# Peripherals.net
KiCad netlist of a schematic drawn in Altium Designer
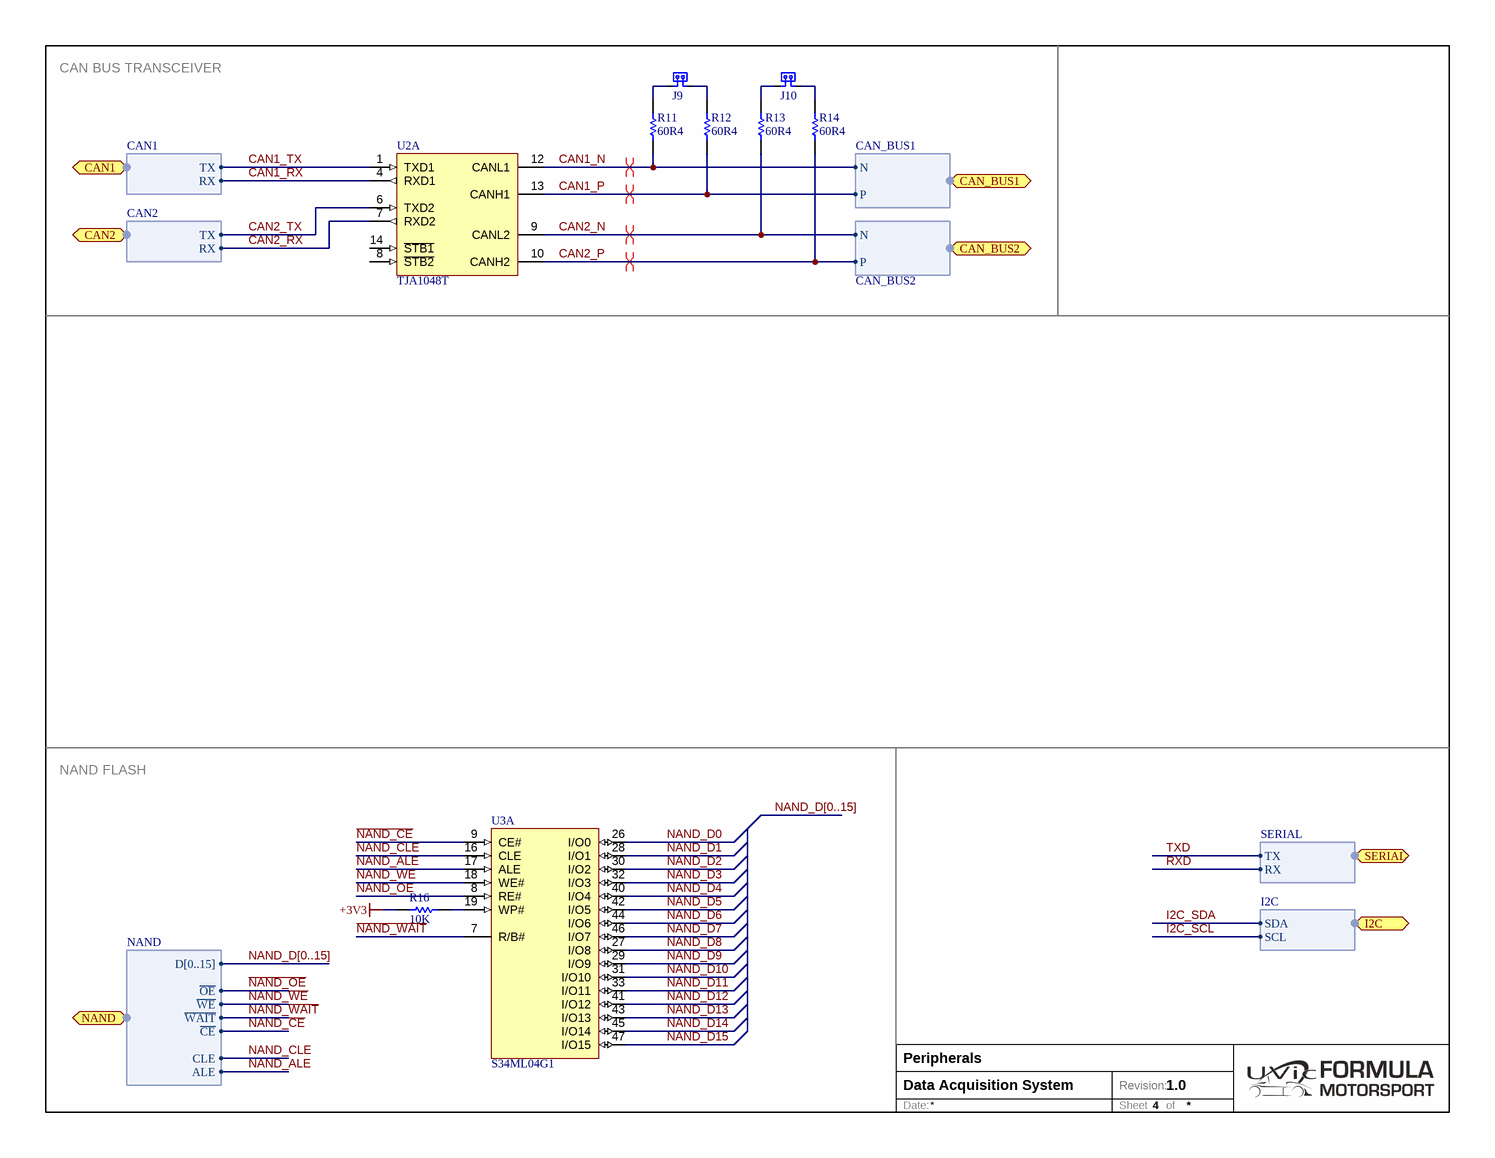
[diagram p0: Peripherals.SchDoc]

(export (version "E")
  (design (tool "Eeschema 10.0.6"))
  (components
    (comp (ref "J9")
      (value "M20-9990246")
      (footprint "M20-9990246")
      (description "2.54mm Header Jumper")
      (libsource (lib "DAQ") (part "JUMPER-1"))
    )
    (comp (ref "J10")
      (value "M20-9990246")
      (footprint "M20-9990246")
      (description "2.54mm Header Jumper")
      (libsource (lib "DAQ") (part "JUMPER-1"))
    )
    (comp (ref "R11")
      (value "60R4")
      (footprint "RES-1206-M")
      (fields
        (field (name "PART NUMBER") "RC1206FR-0760R4L")
        (field (name "TOLERANCE") "±1%")
        (field (name "POWER") "1/4 W")
      )
      (libsource (lib "Resistors") (part "Resistor"))
    )
    (comp (ref "R12")
      (value "60R4")
      (footprint "RES-1206-M")
      (fields
        (field (name "PART NUMBER") "RC1206FR-0760R4L")
        (field (name "TOLERANCE") "±1%")
        (field (name "POWER") "1/4 W")
      )
      (libsource (lib "Resistors") (part "Resistor"))
    )
    (comp (ref "R13")
      (value "60R4")
      (footprint "RES-1206-M")
      (fields
        (field (name "PART NUMBER") "RC1206FR-0760R4L")
        (field (name "TOLERANCE") "±1%")
        (field (name "POWER") "1/4 W")
      )
      (libsource (lib "Resistors") (part "Resistor"))
    )
    (comp (ref "R14")
      (value "60R4")
      (footprint "RES-1206-M")
      (fields
        (field (name "PART NUMBER") "RC1206FR-0760R4L")
        (field (name "TOLERANCE") "±1%")
        (field (name "POWER") "1/4 W")
      )
      (libsource (lib "Resistors") (part "Resistor"))
    )
    (comp (ref "R16")
      (value "10K")
      (footprint "RES-0603-M")
      (fields
        (field (name "PART NUMBER") "RC0603FR-0710KL")
        (field (name "TOLERANCE") "1%")
        (field (name "POWER") "1/10 W")
      )
      (libsource (lib "Resistors") (part "Resistor"))
    )
    (comp (ref "U2")
      (value "TJA1048T")
      (footprint "SOP127P600X175-14N")
      (description "Dual CAN transceiver")
      (libsource (lib "DAQ") (part "TJA1048T"))
    )
    (comp (ref "U3") (value "S34ML04G1") (footprint "48-TSOP") (libsource (lib "DAQ") (part "S34ML04G1")))
  )
  (nets
    (net (code "8") (name "+3V3") (class "Default")
      (node (ref "R16") (pin "2") (pinfunction "2_2") (pintype "passive"))
    )
    (net (code "9") (name "/CAN1_N") (class "Default")
      (node (ref "R11") (pin "2") (pinfunction "2_2") (pintype "passive"))
      (node (ref "U2") (pin "12") (pinfunction "CANL1_12") (pintype "passive"))
    )
    (net (code "10") (name "/CAN1_P") (class "Default")
      (node (ref "R12") (pin "2") (pinfunction "2_2") (pintype "passive"))
      (node (ref "U2") (pin "13") (pinfunction "CANH1_13") (pintype "passive"))
    )
    (net (code "11") (name "/CAN1_RX") (class "Default")
      (node (ref "U2") (pin "4") (pinfunction "RXD1_4") (pintype "output"))
    )
    (net (code "12") (name "/CAN1_TX") (class "Default")
      (node (ref "U2") (pin "1") (pinfunction "TXD1_1") (pintype "input"))
    )
    (net (code "13") (name "/CAN2_N") (class "Default")
      (node (ref "R13") (pin "2") (pinfunction "2_2") (pintype "passive"))
      (node (ref "U2") (pin "9") (pinfunction "CANL2_9") (pintype "passive"))
    )
    (net (code "14") (name "/CAN2_P") (class "Default")
      (node (ref "R14") (pin "2") (pinfunction "2_2") (pintype "passive"))
      (node (ref "U2") (pin "10") (pinfunction "CANH2_10") (pintype "passive"))
    )
    (net (code "15") (name "/CAN2_RX") (class "Default")
      (node (ref "U2") (pin "7") (pinfunction "RXD2_7") (pintype "output"))
    )
    (net (code "16") (name "/CAN2_TX") (class "Default")
      (node (ref "U2") (pin "6") (pinfunction "TXD2_6") (pintype "input"))
    )
    (net (code "19") (name "/NAND_ALE") (class "Default")
      (node (ref "U3") (pin "17") (pinfunction "ALE_17") (pintype "input"))
    )
    (net (code "20") (name "/NAND_CLE") (class "Default")
      (node (ref "U3") (pin "16") (pinfunction "CLE_16") (pintype "input"))
    )
    (net (code "21") (name "/NAND_D0") (class "Default")
      (node (ref "U3") (pin "26") (pinfunction "I/O0_26") (pintype "bidirectional"))
    )
    (net (code "22") (name "/NAND_D1") (class "Default")
      (node (ref "U3") (pin "28") (pinfunction "I/O1_28") (pintype "bidirectional"))
    )
    (net (code "23") (name "/NAND_D2") (class "Default")
      (node (ref "U3") (pin "30") (pinfunction "I/O2_30") (pintype "bidirectional"))
    )
    (net (code "24") (name "/NAND_D3") (class "Default")
      (node (ref "U3") (pin "32") (pinfunction "I/O3_32") (pintype "bidirectional"))
    )
    (net (code "25") (name "/NAND_D4") (class "Default")
      (node (ref "U3") (pin "40") (pinfunction "I/O4_40") (pintype "bidirectional"))
    )
    (net (code "26") (name "/NAND_D5") (class "Default")
      (node (ref "U3") (pin "42") (pinfunction "I/O5_42") (pintype "bidirectional"))
    )
    (net (code "27") (name "/NAND_D6") (class "Default")
      (node (ref "U3") (pin "44") (pinfunction "I/O6_44") (pintype "bidirectional"))
    )
    (net (code "28") (name "/NAND_D7") (class "Default")
      (node (ref "U3") (pin "46") (pinfunction "I/O7_46") (pintype "bidirectional"))
    )
    (net (code "29") (name "/NAND_D8") (class "Default")
      (node (ref "U3") (pin "27") (pinfunction "I/O8_27") (pintype "bidirectional"))
    )
    (net (code "30") (name "/NAND_D9") (class "Default")
      (node (ref "U3") (pin "29") (pinfunction "I/O9_29") (pintype "bidirectional"))
    )
    (net (code "31") (name "/NAND_D10") (class "Default")
      (node (ref "U3") (pin "31") (pinfunction "I/O10_31") (pintype "bidirectional"))
    )
    (net (code "32") (name "/NAND_D11") (class "Default")
      (node (ref "U3") (pin "33") (pinfunction "I/O11_33") (pintype "bidirectional"))
    )
    (net (code "33") (name "/NAND_D12") (class "Default")
      (node (ref "U3") (pin "41") (pinfunction "I/O12_41") (pintype "bidirectional"))
    )
    (net (code "34") (name "/NAND_D13") (class "Default")
      (node (ref "U3") (pin "43") (pinfunction "I/O13_43") (pintype "bidirectional"))
    )
    (net (code "35") (name "/NAND_D14") (class "Default")
      (node (ref "U3") (pin "45") (pinfunction "I/O14_45") (pintype "bidirectional"))
    )
    (net (code "36") (name "/NAND_D15") (class "Default")
      (node (ref "U3") (pin "47") (pinfunction "I/O15_47") (pintype "bidirectional"))
    )
    (net (code "48") (name "/~{NAND_CE}") (class "Default")
      (node (ref "U3") (pin "9") (pinfunction "CE#_9") (pintype "input"))
    )
    (net (code "49") (name "/~{NAND_OE}") (class "Default")
      (node (ref "U3") (pin "8") (pinfunction "RE#_8") (pintype "input"))
    )
    (net (code "50") (name "/~{NAND_WAIT}") (class "Default")
      (node (ref "U3") (pin "7") (pinfunction "R/B#_7") (pintype "tri_state"))
    )
    (net (code "51") (name "/~{NAND_WE}") (class "Default")
      (node (ref "U3") (pin "18") (pinfunction "WE#_18") (pintype "input"))
    )
    (net (code "52") (name "Net-(J9-Pad1)") (class "Default")
      (node (ref "J9") (pin "1") (pinfunction "1_1") (pintype "passive"))
      (node (ref "R11") (pin "1") (pinfunction "1_1") (pintype "passive"))
    )
    (net (code "53") (name "Net-(J9-Pad2)") (class "Default")
      (node (ref "J9") (pin "2") (pinfunction "2_2") (pintype "passive"))
      (node (ref "R12") (pin "1") (pinfunction "1_1") (pintype "passive"))
    )
    (net (code "54") (name "Net-(J10-Pad1)") (class "Default")
      (node (ref "J10") (pin "1") (pinfunction "1_1") (pintype "passive"))
      (node (ref "R13") (pin "1") (pinfunction "1_1") (pintype "passive"))
    )
    (net (code "55") (name "Net-(J10-Pad2)") (class "Default")
      (node (ref "J10") (pin "2") (pinfunction "2_2") (pintype "passive"))
      (node (ref "R14") (pin "1") (pinfunction "1_1") (pintype "passive"))
    )
    (net (code "56") (name "Net-(U3A-WP#)") (class "Default")
      (node (ref "R16") (pin "1") (pinfunction "1_1") (pintype "passive"))
      (node (ref "U3") (pin "19") (pinfunction "WP#_19") (pintype "input"))
    )
    (net (code "57") (name "unconnected-(U2A-~{STB1}-Pad14)") (class "Default")
      (node (ref "U2") (pin "14") (pinfunction "~{STB1}_14") (pintype "input"))
    )
    (net (code "58") (name "unconnected-(U2A-~{STB2}-Pad8)") (class "Default")
      (node (ref "U2") (pin "8") (pinfunction "~{STB2}_8") (pintype "input"))
    )
  )
)
